# Hierarchal.net
KiCad netlist of a schematic drawn in Altium Designer
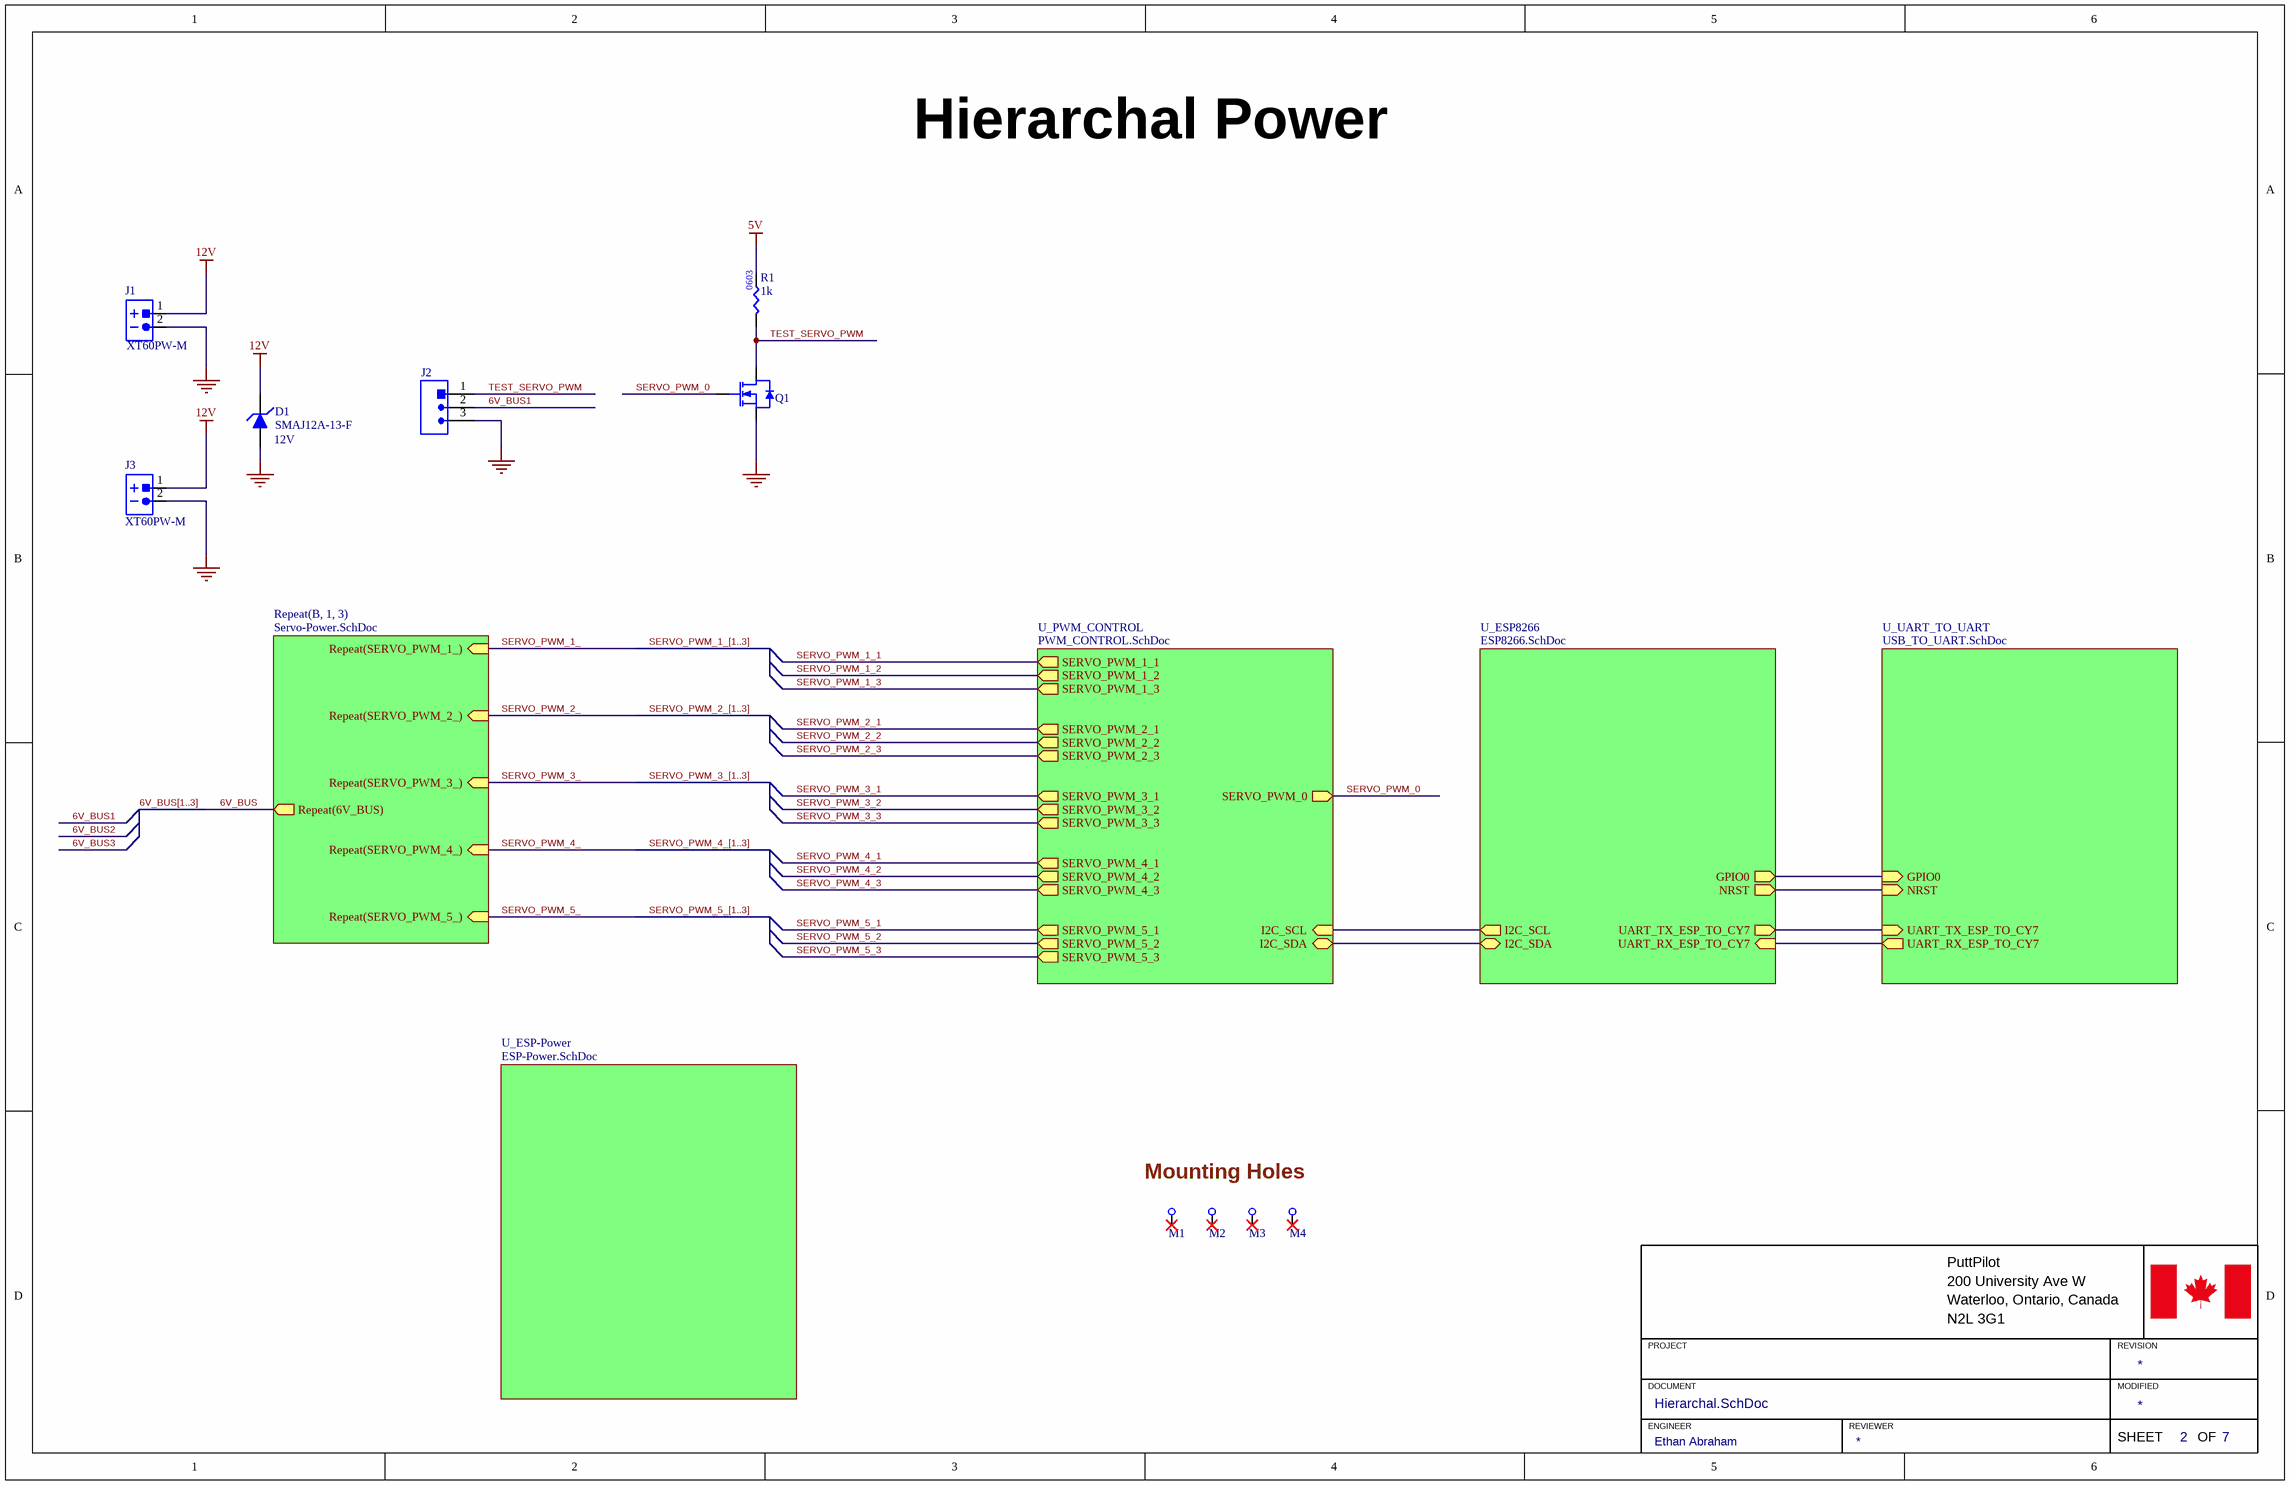
[diagram p0: Hierarchal.SchDoc]

(export (version "E")
  (design (tool "Eeschema 10.0.6"))
  (components
    (comp (ref "D1")
      (value "SMAJ12A-13-F")
      (footprint "SMAJ12A-13-F")
      (description "TVS DIODE 12VWM")
      (fields (field (name "MANUFACTURER") "Diodes") (field (name "REP PK REVERSE VOLTAGE-MAX") "12V"))
      (libsource (lib "PuttPilot") (part "SMAJ12A-13-F"))
    )
    (comp (ref "J1")
      (value "XT60PW-M")
      (footprint "XT60PW-M")
      (description "XT60PW Male")
      (fields (field (name "MANUFACTURER") "Unclassified"))
      (libsource (lib "PuttPilot") (part "XT60PW-M"))
    )
    (comp (ref "J2")
      (value "TSW-101-08-G-T-RA")
      (footprint "HEADER_3POS_R/A_2.54MM")
      (description "CONN HEADER R/A 3POS 2.54MM")
      (libsource (lib "PuttPilot") (part "TSW-101-08-G-T-RA"))
    )
    (comp (ref "J3")
      (value "XT60PW-M")
      (footprint "XT60PW-M")
      (description "XT60PW Male")
      (fields (field (name "MANUFACTURER") "Unclassified"))
      (libsource (lib "PuttPilot") (part "XT60PW-M"))
    )
    (comp (ref "M1")
      (value ".HOLE_M3")
      (footprint ".HOLE_M3")
      (description ".HOLE M3")
      (libsource (lib "PuttPilot") (part ".HOLE_M3"))
    )
    (comp (ref "M2")
      (value ".HOLE_M3")
      (footprint ".HOLE_M3")
      (description ".HOLE M3")
      (libsource (lib "PuttPilot") (part ".HOLE_M3"))
    )
    (comp (ref "M3")
      (value ".HOLE_M3")
      (footprint ".HOLE_M3")
      (description ".HOLE M3")
      (libsource (lib "PuttPilot") (part ".HOLE_M3"))
    )
    (comp (ref "M4")
      (value ".HOLE_M3")
      (footprint ".HOLE_M3")
      (description ".HOLE M3")
      (libsource (lib "PuttPilot") (part ".HOLE_M3"))
    )
    (comp (ref "Q1")
      (value "DMN6140L-7")
      (footprint ".SOT-23-3")
      (description "MOSFET N-CH 60V 1.6A SOT-23")
      (fields (field (name "MANUFACTURER") "Diodes"))
      (libsource (lib "PuttPilot") (part "DMN6140L-7"))
    )
    (comp (ref "R1")
      (value "RC0603FR-071KL")
      (footprint ".RES_0603")
      (description "RES 1K OHM 0603")
      (fields
        (field (name "MANUFACTURER") "Yageo")
        (field (name "TOLERANCE") "1%")
        (field (name "RESISTANCE") "1k")
      )
      (libsource (lib "PuttPilot") (part "RC0603FR-071KL"))
    )
  )
  (nets
    (net (code "2") (name "/6V_BUS1") (class "Default")
      (node (ref "J2") (pin "2") (pinfunction "2_2") (pintype "passive"))
    )
    (net (code "10") (name "/SERVO_PWM_0") (class "Default")
      (node (ref "Q1") (pin "1") (pinfunction "Gate_1") (pintype "passive"))
    )
    (net (code "36") (name "/TEST_SERVO_PWM") (class "Default")
      (node (ref "J2") (pin "1") (pinfunction "1_1") (pintype "passive"))
      (node (ref "Q1") (pin "3") (pinfunction "Drain_3") (pintype "passive"))
      (node (ref "R1") (pin "1") (pinfunction "1_1") (pintype "passive"))
    )
    (net (code "39") (name "5V") (class "Default")
      (node (ref "R1") (pin "2") (pinfunction "2_2") (pintype "passive"))
    )
    (net (code "40") (name "12V") (class "Default")
      (node (ref "D1") (pin "2") (pinfunction "Pin_2_2") (pintype "passive"))
      (node (ref "J1") (pin "1") (pinfunction "1_1") (pintype "passive"))
      (node (ref "J3") (pin "1") (pinfunction "1_1") (pintype "passive"))
    )
    (net (code "41") (name "GND") (class "Default")
      (node (ref "D1") (pin "1") (pinfunction "Pin_1_1") (pintype "passive"))
      (node (ref "J1") (pin "2") (pinfunction "2_2") (pintype "passive"))
      (node (ref "J2") (pin "3") (pinfunction "3_3") (pintype "passive"))
      (node (ref "J3") (pin "2") (pinfunction "2_2") (pintype "passive"))
      (node (ref "Q1") (pin "2") (pinfunction "Source_2") (pintype "passive"))
    )
    (net (code "42") (name "unconnected-(M1-Pad1)") (class "Default")
      (node (ref "M1") (pin "1") (pinfunction "1_1") (pintype "passive+no_connect"))
    )
    (net (code "43") (name "unconnected-(M2-Pad1)") (class "Default")
      (node (ref "M2") (pin "1") (pinfunction "1_1") (pintype "passive+no_connect"))
    )
    (net (code "44") (name "unconnected-(M3-Pad1)") (class "Default")
      (node (ref "M3") (pin "1") (pinfunction "1_1") (pintype "passive+no_connect"))
    )
    (net (code "45") (name "unconnected-(M4-Pad1)") (class "Default")
      (node (ref "M4") (pin "1") (pinfunction "1_1") (pintype "passive+no_connect"))
    )
  )
)
